# Analog_MEMS_Microphone_Breakout_ICS40180.net
KiCad netlist of a schematic drawn in EAGLE
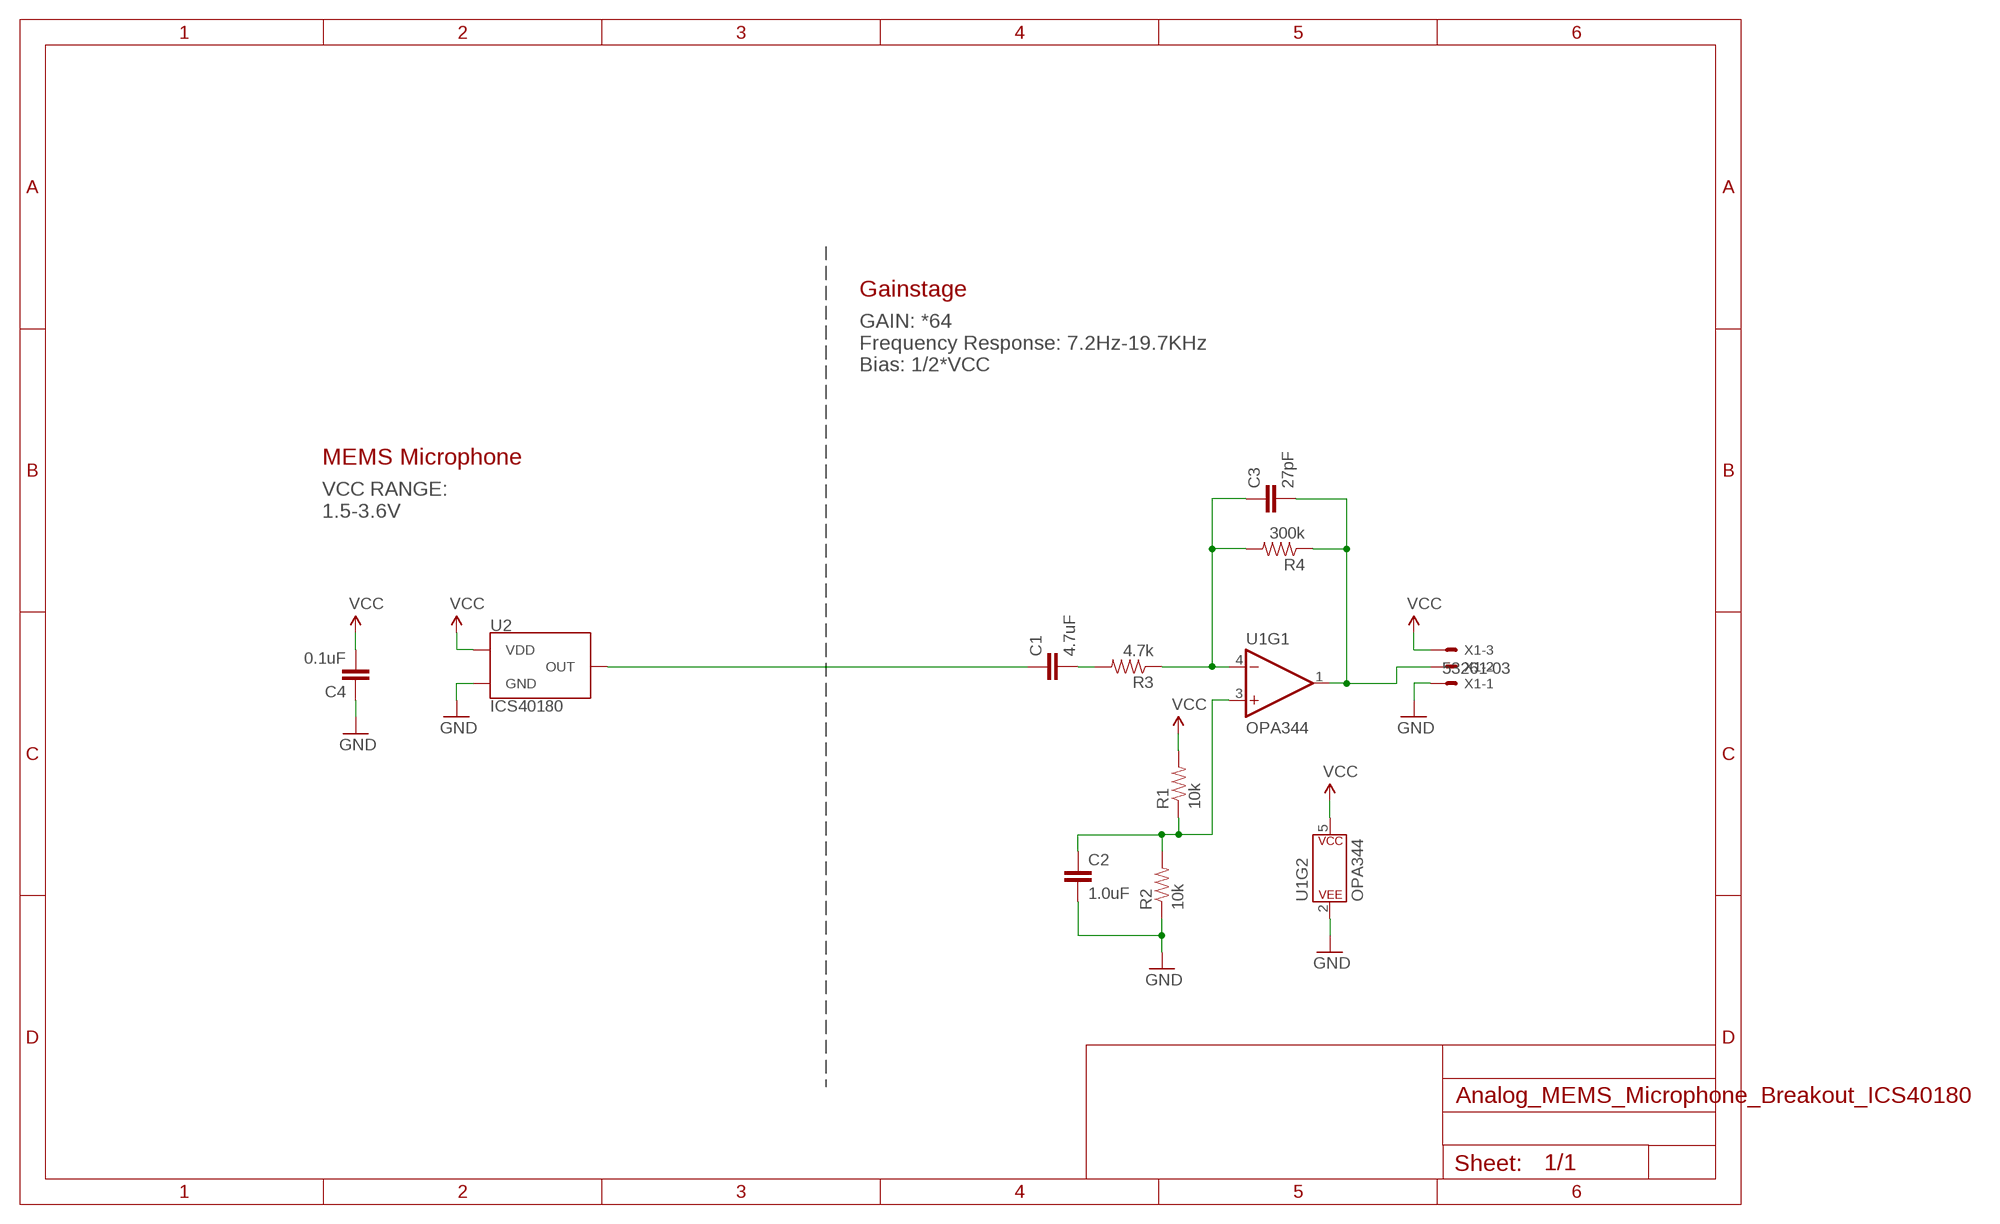
[diagram p0: schematic, sheet 1]

(export (version "E")
  (design (tool "Eeschema 10.0.6"))
  (components
    (comp (ref "C1")
      (value "4.7uF")
      (footprint "eagle-import:0603")
      (libsource (lib "eagle-import") (part "4.7UF-0603-6.3V-(10%)"))
    )
    (comp (ref "C2")
      (value "1.0uF")
      (footprint "eagle-import:0603")
      (libsource (lib "eagle-import") (part "1.0UF-0603-16V-10%"))
    )
    (comp (ref "C3")
      (value "27pF")
      (footprint "eagle-import:0603")
      (libsource (lib "eagle-import") (part "27PF-0603-50V-5%"))
    )
    (comp (ref "C4")
      (value "0.1uF")
      (footprint "eagle-import:0603")
      (libsource (lib "eagle-import") (part "0.1UF-0603-25V-(+80/-20%)"))
    )
    (comp (ref "R1")
      (value "10k")
      (footprint "eagle-import:0603")
      (libsource (lib "eagle-import") (part "10KOHM-0603-1/10W-1%"))
    )
    (comp (ref "R2")
      (value "10k")
      (footprint "eagle-import:0603")
      (libsource (lib "eagle-import") (part "10KOHM-0603-1/10W-1%"))
    )
    (comp (ref "R3")
      (value "4.7k")
      (footprint "eagle-import:0603")
      (libsource (lib "eagle-import") (part "4.7KOHM-0603-1/10W-1%"))
    )
    (comp (ref "R4")
      (value "300k")
      (footprint "eagle-import:0603")
      (libsource (lib "eagle-import") (part "300KOHM-0603-1/10W-1%"))
    )
    (comp (ref "U1")
      (value "OPA344")
      (footprint "eagle-import:SOT23-5")
      (libsource (lib "eagle-import") (part "OPA344"))
    )
    (comp (ref "U2")
      (value "ICS40180")
      (footprint "eagle-import:ICS40180")
      (libsource (lib "eagle-import") (part "ICS40180"))
    )
    (comp (ref "X1")
      (value "53261-03")
      (footprint "eagle-import:53261-03")
      (fields (field (name "MF") "MOLEX") (field (name "MPN") "53261-0390"))
      (libsource (lib "eagle-import") (part "53?-03261"))
    )
  )
  (nets
    (net (code "1") (name "GND") (class "Default")
      (node (ref "C2") (pin "2") (pinfunction "2_2") (pintype "passive"))
      (node (ref "C4") (pin "1") (pinfunction "1_1") (pintype "passive"))
      (node (ref "R2") (pin "1") (pinfunction "1_1") (pintype "passive"))
      (node (ref "U1") (pin "2") (pinfunction "P$V-_2") (pintype "bidirectional"))
      (node (ref "U2") (pin "2") (pinfunction "GND_2") (pintype "bidirectional"))
      (node (ref "U2") (pin "3") (pinfunction "GND_3") (pintype "bidirectional"))
      (node (ref "U2") (pin "4") (pinfunction "GND_4") (pintype "bidirectional"))
      (node (ref "X1") (pin "1") (pinfunction "S_1") (pintype "passive"))
    )
    (net (code "2") (name "Net-(C1-Pad2)") (class "Default")
      (node (ref "C1") (pin "2") (pinfunction "2_2") (pintype "passive"))
      (node (ref "R3") (pin "2") (pinfunction "2_2") (pintype "passive"))
    )
    (net (code "3") (name "Net-(U1A-+IN)") (class "Default")
      (node (ref "C2") (pin "1") (pinfunction "1_1") (pintype "passive"))
      (node (ref "R1") (pin "1") (pinfunction "1_1") (pintype "passive"))
      (node (ref "R2") (pin "2") (pinfunction "2_2") (pintype "passive"))
      (node (ref "U1") (pin "3") (pinfunction "+IN_3") (pintype "input"))
    )
    (net (code "4") (name "Net-(U1A--IN)") (class "Default")
      (node (ref "C3") (pin "1") (pinfunction "1_1") (pintype "passive"))
      (node (ref "R3") (pin "1") (pinfunction "1_1") (pintype "passive"))
      (node (ref "R4") (pin "2") (pinfunction "2_2") (pintype "passive"))
      (node (ref "U1") (pin "4") (pinfunction "-IN_4") (pintype "input"))
    )
    (net (code "5") (name "Net-(U1A-OUT)") (class "Default")
      (node (ref "C3") (pin "2") (pinfunction "2_2") (pintype "passive"))
      (node (ref "R4") (pin "1") (pinfunction "1_1") (pintype "passive"))
      (node (ref "U1") (pin "1") (pinfunction "OUT_1") (pintype "output"))
      (node (ref "X1") (pin "2") (pinfunction "S_2") (pintype "passive"))
    )
    (net (code "6") (name "Net-(U2-OUT)") (class "Default")
      (node (ref "C1") (pin "1") (pinfunction "1_1") (pintype "passive"))
      (node (ref "U2") (pin "1") (pinfunction "OUT_1") (pintype "bidirectional"))
    )
    (net (code "7") (name "VCC") (class "Default")
      (node (ref "C4") (pin "2") (pinfunction "2_2") (pintype "passive"))
      (node (ref "R1") (pin "2") (pinfunction "2_2") (pintype "passive"))
      (node (ref "U1") (pin "5") (pinfunction "P$V+_5") (pintype "bidirectional"))
      (node (ref "U2") (pin "5") (pinfunction "VDD_5") (pintype "bidirectional"))
      (node (ref "X1") (pin "3") (pinfunction "S_3") (pintype "passive"))
    )
  )
)
